# Proximity-Sensor-Schematic.net
KiCad netlist of a schematic drawn in Altium Designer
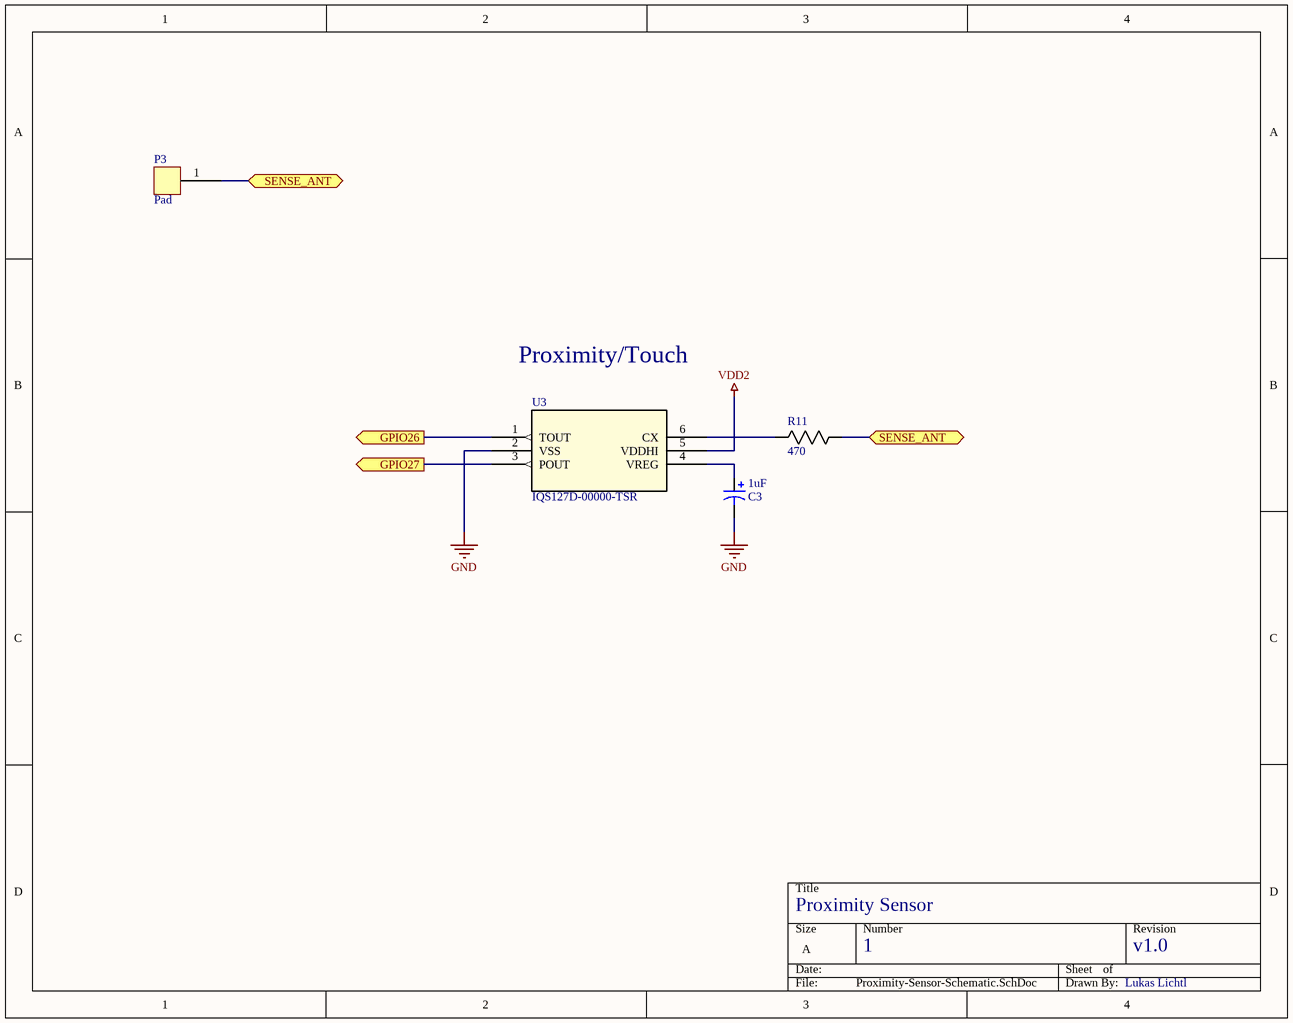
[diagram p0: Proximity-Sensor-Schematic.SchDoc]

(export (version "E")
  (design (tool "Eeschema 10.0.6"))
  (components
    (comp (ref "C3")
      (value "1uF")
      (footprint "C0805")
      (description "Polarized Capacitor (Surface Mount)")
      (fields (field (name "Comment") "Cap Pol3") (field (name "PUBLISHER") "Altium Limited"))
      (libsource (lib "Miscellaneous Devices") (part "Cap Pol3"))
    )
    (comp (ref "P3") (value "Pad") (footprint "Simple-PAD-PCB") (libsource (lib "Simple-PAD") (part "Pad")))
    (comp (ref "R11")
      (value "470")
      (footprint "RC0603N_YAG")
      (description "No Description Available")
      (libsource (lib "RC0603FR-07470RL") (part "RC0603FR-07470RL"))
    )
    (comp (ref "U3")
      (value "IQS127D-00000-TSR")
      (footprint "TSOT23-6_AZQ")
      (description "No Description Available")
      (libsource (lib "IQS127D-00000-TSR") (part "IQS127D-00000-TSR"))
    )
  )
  (nets
    (net (code "1") (name "/GPIO26") (class "Default")
      (node (ref "U3") (pin "1") (pinfunction "TOUT_1") (pintype "output"))
    )
    (net (code "2") (name "/GPIO27") (class "Default")
      (node (ref "U3") (pin "3") (pinfunction "POUT_3") (pintype "output"))
    )
    (net (code "3") (name "/SENSE_ANT") (class "Default")
      (node (ref "P3") (pin "1") (pintype "passive"))
      (node (ref "R11") (pin "1") (pinfunction "1_1") (pintype "passive"))
    )
    (net (code "4") (name "GND") (class "Default")
      (node (ref "C3") (pin "2") (pinfunction "2_2") (pintype "passive"))
      (node (ref "U3") (pin "2") (pinfunction "VSS_2") (pintype "power_in"))
    )
    (net (code "5") (name "Net-(U3-CX)") (class "Default")
      (node (ref "R11") (pin "2") (pinfunction "2_2") (pintype "passive"))
      (node (ref "U3") (pin "6") (pinfunction "CX_6") (pintype "passive"))
    )
    (net (code "6") (name "Net-(U3-VREG)") (class "Default")
      (node (ref "C3") (pin "1") (pinfunction "1_1") (pintype "passive"))
      (node (ref "U3") (pin "4") (pinfunction "VREG_4") (pintype "power_in"))
    )
    (net (code "7") (name "VDD2") (class "Default")
      (node (ref "U3") (pin "5") (pinfunction "VDDHI_5") (pintype "power_in"))
    )
  )
)
